# zik-pcb-gpu-f405.net
KiCad netlist of a schematic drawn in EAGLE
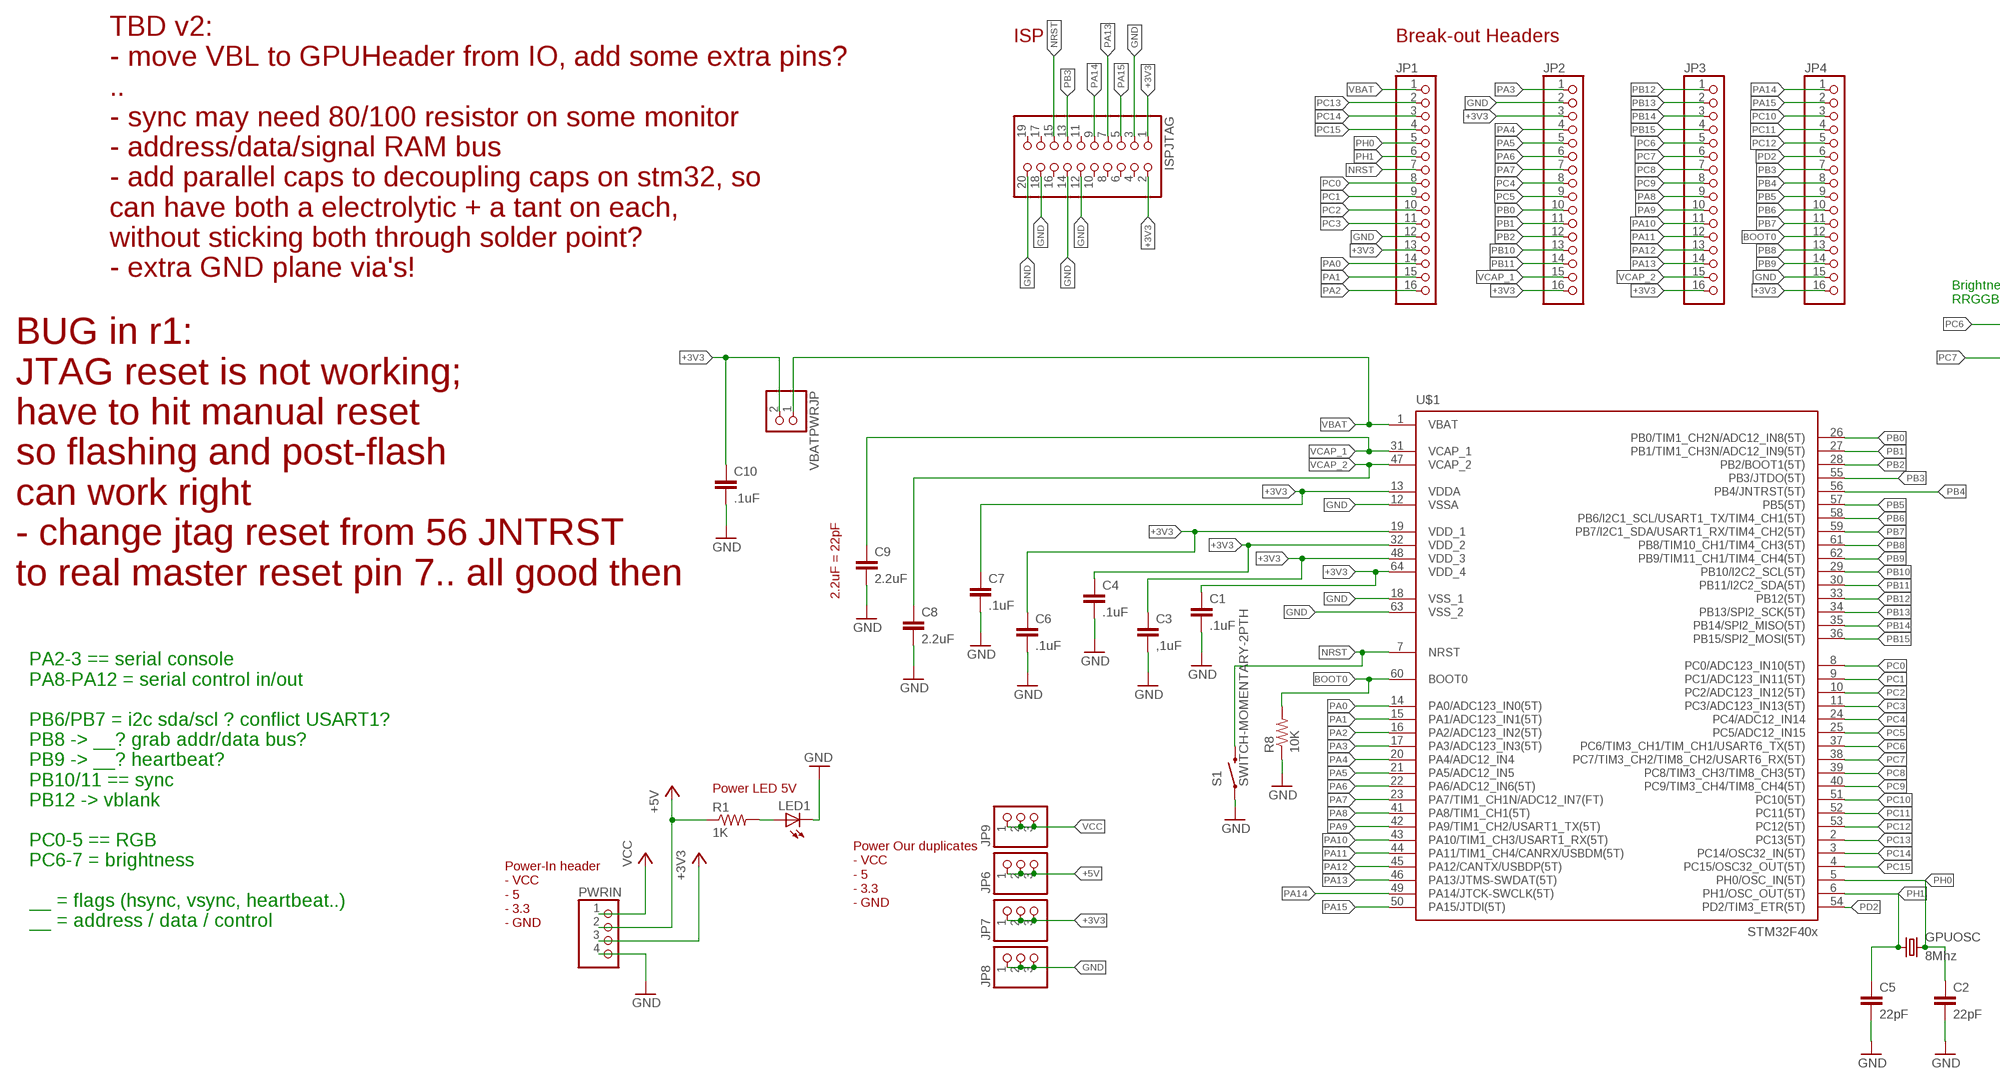
[diagram p0: schematic, sheet 1, part 1 of 2]
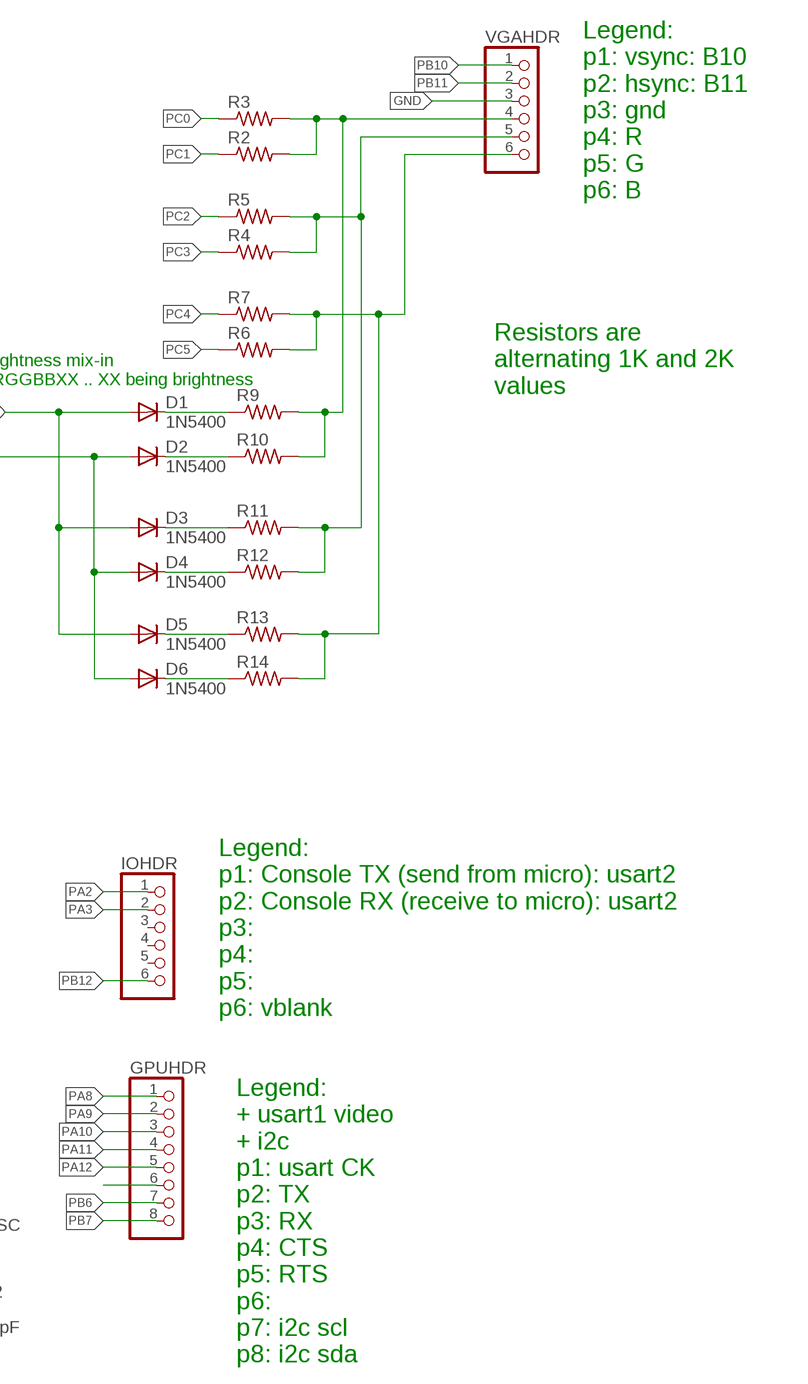
[diagram p1: schematic, sheet 1, part 2 of 2]

(export (version "E")
  (design (tool "Eeschema 10.0.6"))
  (components
    (comp (ref "C1")
      (value ".1uF")
      (footprint "eagle-import:C025-025X050")
      (libsource (lib "eagle-import") (part "C-EU025-025X050"))
    )
    (comp (ref "C2")
      (value "22pF")
      (footprint "eagle-import:C025-025X050")
      (libsource (lib "eagle-import") (part "C-EU025-025X050"))
    )
    (comp (ref "C3")
      (value ",1uF")
      (footprint "eagle-import:C025-025X050")
      (libsource (lib "eagle-import") (part "C-EU025-025X050"))
    )
    (comp (ref "C4")
      (value ".1uF")
      (footprint "eagle-import:C025-025X050")
      (libsource (lib "eagle-import") (part "C-EU025-025X050"))
    )
    (comp (ref "C5")
      (value "22pF")
      (footprint "eagle-import:C025-025X050")
      (libsource (lib "eagle-import") (part "C-EU025-025X050"))
    )
    (comp (ref "C6")
      (value ".1uF")
      (footprint "eagle-import:C025-025X050")
      (libsource (lib "eagle-import") (part "C-EU025-025X050"))
    )
    (comp (ref "C7")
      (value ".1uF")
      (footprint "eagle-import:C025-025X050")
      (libsource (lib "eagle-import") (part "C-EU025-025X050"))
    )
    (comp (ref "C8")
      (value "2.2uF")
      (footprint "eagle-import:C025-025X050")
      (libsource (lib "eagle-import") (part "C-EU025-025X050"))
    )
    (comp (ref "C9")
      (value "2.2uF")
      (footprint "eagle-import:C025-025X050")
      (libsource (lib "eagle-import") (part "C-EU025-025X050"))
    )
    (comp (ref "C10")
      (value ".1uF")
      (footprint "eagle-import:C025-025X050")
      (libsource (lib "eagle-import") (part "C-EU025-025X050"))
    )
    (comp (ref "D1")
      (value "1N5400")
      (footprint "eagle-import:DO201-15")
      (libsource (lib "eagle-import") (part "1N5400"))
    )
    (comp (ref "D2")
      (value "1N5400")
      (footprint "eagle-import:DO201-15")
      (libsource (lib "eagle-import") (part "1N5400"))
    )
    (comp (ref "D3")
      (value "1N5400")
      (footprint "eagle-import:DO201-15")
      (libsource (lib "eagle-import") (part "1N5400"))
    )
    (comp (ref "D4")
      (value "1N5400")
      (footprint "eagle-import:DO201-15")
      (libsource (lib "eagle-import") (part "1N5400"))
    )
    (comp (ref "D5")
      (value "1N5400")
      (footprint "eagle-import:DO201-15")
      (libsource (lib "eagle-import") (part "1N5400"))
    )
    (comp (ref "D6")
      (value "1N5400")
      (footprint "eagle-import:DO201-15")
      (libsource (lib "eagle-import") (part "1N5400"))
    )
    (comp (ref "GPUHDR")
      (value "PINHD-1X8")
      (footprint "eagle-import:1X08")
      (libsource (lib "eagle-import") (part "PINHD-1X8"))
    )
    (comp (ref "GPUOSC")
      (value "8Mhz")
      (footprint "eagle-import:HC49US")
      (libsource (lib "eagle-import") (part "CRYSTALHC49US"))
    )
    (comp (ref "IOHDR")
      (value "PINHD-1X6")
      (footprint "eagle-import:1X06")
      (libsource (lib "eagle-import") (part "PINHD-1X6"))
    )
    (comp (ref "ISPJTAG")
      (value "PINHD-2X10")
      (footprint "eagle-import:2X10")
      (libsource (lib "eagle-import") (part "PINHD-2X10"))
    )
    (comp (ref "JP1")
      (value "PINHD-1X16")
      (footprint "eagle-import:1X16")
      (libsource (lib "eagle-import") (part "PINHD-1X16"))
    )
    (comp (ref "JP2")
      (value "PINHD-1X16")
      (footprint "eagle-import:1X16")
      (libsource (lib "eagle-import") (part "PINHD-1X16"))
    )
    (comp (ref "JP3")
      (value "PINHD-1X16")
      (footprint "eagle-import:1X16")
      (libsource (lib "eagle-import") (part "PINHD-1X16"))
    )
    (comp (ref "JP4")
      (value "PINHD-1X16")
      (footprint "eagle-import:1X16")
      (libsource (lib "eagle-import") (part "PINHD-1X16"))
    )
    (comp (ref "JP6")
      (value "PINHD-1X3")
      (footprint "eagle-import:1X03")
      (libsource (lib "eagle-import") (part "PINHD-1X3"))
    )
    (comp (ref "JP7")
      (value "PINHD-1X3")
      (footprint "eagle-import:1X03")
      (libsource (lib "eagle-import") (part "PINHD-1X3"))
    )
    (comp (ref "JP8")
      (value "PINHD-1X3")
      (footprint "eagle-import:1X03")
      (libsource (lib "eagle-import") (part "PINHD-1X3"))
    )
    (comp (ref "JP9")
      (value "PINHD-1X3")
      (footprint "eagle-import:1X03")
      (libsource (lib "eagle-import") (part "PINHD-1X3"))
    )
    (comp (ref "LED1")
      (value "LED5MM")
      (footprint "eagle-import:LED5MM")
      (libsource (lib "eagle-import") (part "LED5MM"))
    )
    (comp (ref "PWRIN")
      (value "PINHD-1X4")
      (footprint "eagle-import:1X04")
      (libsource (lib "eagle-import") (part "PINHD-1X4"))
    )
    (comp (ref "R1")
      (value "1K")
      (footprint "eagle-import:0207_10")
      (libsource (lib "eagle-import") (part "R-US_0207/10"))
    )
    (comp (ref "R2")
      (value "R-US_0207/10")
      (footprint "eagle-import:0207_10")
      (libsource (lib "eagle-import") (part "R-US_0207/10"))
    )
    (comp (ref "R3")
      (value "R-US_0207/10")
      (footprint "eagle-import:0207_10")
      (libsource (lib "eagle-import") (part "R-US_0207/10"))
    )
    (comp (ref "R4")
      (value "R-US_0207/10")
      (footprint "eagle-import:0207_10")
      (libsource (lib "eagle-import") (part "R-US_0207/10"))
    )
    (comp (ref "R5")
      (value "R-US_0207/10")
      (footprint "eagle-import:0207_10")
      (libsource (lib "eagle-import") (part "R-US_0207/10"))
    )
    (comp (ref "R6")
      (value "R-US_0207/10")
      (footprint "eagle-import:0207_10")
      (libsource (lib "eagle-import") (part "R-US_0207/10"))
    )
    (comp (ref "R7")
      (value "R-US_0207/10")
      (footprint "eagle-import:0207_10")
      (libsource (lib "eagle-import") (part "R-US_0207/10"))
    )
    (comp (ref "R8")
      (value "10K")
      (footprint "eagle-import:0207_10")
      (libsource (lib "eagle-import") (part "R-US_0207/10"))
    )
    (comp (ref "R9")
      (value "R-US_0207/10")
      (footprint "eagle-import:0207_10")
      (libsource (lib "eagle-import") (part "R-US_0207/10"))
    )
    (comp (ref "R10")
      (value "R-US_0207/10")
      (footprint "eagle-import:0207_10")
      (libsource (lib "eagle-import") (part "R-US_0207/10"))
    )
    (comp (ref "R11")
      (value "R-US_0207/10")
      (footprint "eagle-import:0207_10")
      (libsource (lib "eagle-import") (part "R-US_0207/10"))
    )
    (comp (ref "R12")
      (value "R-US_0207/10")
      (footprint "eagle-import:0207_10")
      (libsource (lib "eagle-import") (part "R-US_0207/10"))
    )
    (comp (ref "R13")
      (value "R-US_0207/10")
      (footprint "eagle-import:0207_10")
      (libsource (lib "eagle-import") (part "R-US_0207/10"))
    )
    (comp (ref "R14")
      (value "R-US_0207/10")
      (footprint "eagle-import:0207_10")
      (libsource (lib "eagle-import") (part "R-US_0207/10"))
    )
    (comp (ref "S1")
      (value "SWITCH-MOMENTARY-2PTH")
      (footprint "eagle-import:TACTILE-PTH")
      (libsource (lib "eagle-import") (part "SWITCH-MOMENTARY-2PTH"))
    )
    (comp (ref "U$1")
      (value "STM32F405R")
      (footprint "eagle-import:TQFP64")
      (libsource (lib "eagle-import") (part "STM32F405R"))
    )
    (comp (ref "VBATPWRJP")
      (value "PINHD-1X2")
      (footprint "eagle-import:1X02")
      (libsource (lib "eagle-import") (part "PINHD-1X2"))
    )
    (comp (ref "VGAHDR")
      (value "PINHD-1X6")
      (footprint "eagle-import:1X06")
      (libsource (lib "eagle-import") (part "PINHD-1X6"))
    )
  )
  (nets
    (net (code "1") (name "+3V3") (class "Default")
      (node (ref "C1") (pin "1") (pinfunction "1_1") (pintype "passive"))
      (node (ref "C10") (pin "1") (pinfunction "1_1") (pintype "passive"))
      (node (ref "C3") (pin "1") (pinfunction "1_1") (pintype "passive"))
      (node (ref "C4") (pin "1") (pinfunction "1_1") (pintype "passive"))
      (node (ref "C6") (pin "1") (pinfunction "1_1") (pintype "passive"))
      (node (ref "C7") (pin "1") (pinfunction "1_1") (pintype "passive"))
      (node (ref "ISPJTAG") (pin "1") (pinfunction "1_1") (pintype "passive"))
      (node (ref "ISPJTAG") (pin "2") (pinfunction "2_2") (pintype "passive"))
      (node (ref "JP1") (pin "13") (pinfunction "13_13") (pintype "passive"))
      (node (ref "JP2") (pin "16") (pinfunction "16_16") (pintype "passive"))
      (node (ref "JP2") (pin "3") (pinfunction "3_3") (pintype "passive"))
      (node (ref "JP3") (pin "16") (pinfunction "16_16") (pintype "passive"))
      (node (ref "JP4") (pin "16") (pinfunction "16_16") (pintype "passive"))
      (node (ref "JP7") (pin "1") (pinfunction "1_1") (pintype "passive"))
      (node (ref "JP7") (pin "2") (pinfunction "2_2") (pintype "passive"))
      (node (ref "JP7") (pin "3") (pinfunction "3_3") (pintype "passive"))
      (node (ref "PWRIN") (pin "3") (pinfunction "3_3") (pintype "passive"))
      (node (ref "U$1") (pin "13") (pinfunction "VDDA_13") (pintype "bidirectional"))
      (node (ref "U$1") (pin "19") (pinfunction "VDD_1_19") (pintype "bidirectional"))
      (node (ref "U$1") (pin "32") (pinfunction "VDD_2_32") (pintype "bidirectional"))
      (node (ref "U$1") (pin "48") (pinfunction "VDD_3_48") (pintype "bidirectional"))
      (node (ref "U$1") (pin "64") (pinfunction "VDD_4_64") (pintype "bidirectional"))
      (node (ref "VBATPWRJP") (pin "2") (pinfunction "2_2") (pintype "passive"))
    )
    (net (code "2") (name "+5V") (class "Default")
      (node (ref "JP6") (pin "1") (pinfunction "1_1") (pintype "passive"))
      (node (ref "JP6") (pin "2") (pinfunction "2_2") (pintype "passive"))
      (node (ref "JP6") (pin "3") (pinfunction "3_3") (pintype "passive"))
      (node (ref "PWRIN") (pin "2") (pinfunction "2_2") (pintype "passive"))
      (node (ref "R1") (pin "1") (pinfunction "1_1") (pintype "passive"))
    )
    (net (code "3") (name "BOOT0") (class "Default")
      (node (ref "JP4") (pin "12") (pinfunction "12_12") (pintype "passive"))
      (node (ref "R8") (pin "2") (pinfunction "2_2") (pintype "passive"))
      (node (ref "U$1") (pin "60") (pinfunction "BOOT0_60") (pintype "bidirectional"))
    )
    (net (code "4") (name "GND") (class "Default")
      (node (ref "C1") (pin "2") (pinfunction "2_2") (pintype "passive"))
      (node (ref "C10") (pin "2") (pinfunction "2_2") (pintype "passive"))
      (node (ref "C2") (pin "2") (pinfunction "2_2") (pintype "passive"))
      (node (ref "C3") (pin "2") (pinfunction "2_2") (pintype "passive"))
      (node (ref "C4") (pin "2") (pinfunction "2_2") (pintype "passive"))
      (node (ref "C5") (pin "2") (pinfunction "2_2") (pintype "passive"))
      (node (ref "C6") (pin "2") (pinfunction "2_2") (pintype "passive"))
      (node (ref "C7") (pin "2") (pinfunction "2_2") (pintype "passive"))
      (node (ref "C8") (pin "2") (pinfunction "2_2") (pintype "passive"))
      (node (ref "C9") (pin "2") (pinfunction "2_2") (pintype "passive"))
      (node (ref "ISPJTAG") (pin "12") (pinfunction "12_12") (pintype "passive"))
      (node (ref "ISPJTAG") (pin "14") (pinfunction "14_14") (pintype "passive"))
      (node (ref "ISPJTAG") (pin "18") (pinfunction "18_18") (pintype "passive"))
      (node (ref "ISPJTAG") (pin "20") (pinfunction "20_20") (pintype "passive"))
      (node (ref "ISPJTAG") (pin "3") (pinfunction "3_3") (pintype "passive"))
      (node (ref "JP1") (pin "12") (pinfunction "12_12") (pintype "passive"))
      (node (ref "JP2") (pin "2") (pinfunction "2_2") (pintype "passive"))
      (node (ref "JP4") (pin "15") (pinfunction "15_15") (pintype "passive"))
      (node (ref "JP8") (pin "1") (pinfunction "1_1") (pintype "passive"))
      (node (ref "JP8") (pin "2") (pinfunction "2_2") (pintype "passive"))
      (node (ref "JP8") (pin "3") (pinfunction "3_3") (pintype "passive"))
      (node (ref "LED1") (pin "K") (pinfunction "C_K") (pintype "passive"))
      (node (ref "PWRIN") (pin "4") (pinfunction "4_4") (pintype "passive"))
      (node (ref "R8") (pin "1") (pinfunction "1_1") (pintype "passive"))
      (node (ref "S1") (pin "1") (pinfunction "1_1") (pintype "passive"))
      (node (ref "U$1") (pin "12") (pinfunction "VSSA_12") (pintype "bidirectional"))
      (node (ref "U$1") (pin "18") (pinfunction "VSS_1_18") (pintype "bidirectional"))
      (node (ref "U$1") (pin "63") (pinfunction "VSS_2_63") (pintype "bidirectional"))
      (node (ref "VGAHDR") (pin "3") (pinfunction "3_3") (pintype "passive"))
    )
    (net (code "5") (name "NRST") (class "Default")
      (node (ref "ISPJTAG") (pin "15") (pinfunction "15_15") (pintype "passive"))
      (node (ref "JP1") (pin "7") (pinfunction "7_7") (pintype "passive"))
      (node (ref "S1") (pin "3") (pinfunction "2_3") (pintype "passive"))
      (node (ref "U$1") (pin "7") (pinfunction "NRST_7") (pintype "bidirectional"))
    )
    (net (code "6") (name "Net-(D1-PadC)") (class "Default")
      (node (ref "D1") (pin "C") (pinfunction "C_C") (pintype "passive"))
      (node (ref "R9") (pin "1") (pinfunction "1_1") (pintype "passive"))
    )
    (net (code "7") (name "Net-(D2-PadC)") (class "Default")
      (node (ref "D2") (pin "C") (pinfunction "C_C") (pintype "passive"))
      (node (ref "R10") (pin "1") (pinfunction "1_1") (pintype "passive"))
    )
    (net (code "8") (name "Net-(D3-PadC)") (class "Default")
      (node (ref "D3") (pin "C") (pinfunction "C_C") (pintype "passive"))
      (node (ref "R11") (pin "1") (pinfunction "1_1") (pintype "passive"))
    )
    (net (code "9") (name "Net-(D4-PadC)") (class "Default")
      (node (ref "D4") (pin "C") (pinfunction "C_C") (pintype "passive"))
      (node (ref "R12") (pin "1") (pinfunction "1_1") (pintype "passive"))
    )
    (net (code "10") (name "Net-(D5-PadC)") (class "Default")
      (node (ref "D5") (pin "C") (pinfunction "C_C") (pintype "passive"))
      (node (ref "R13") (pin "1") (pinfunction "1_1") (pintype "passive"))
    )
    (net (code "11") (name "Net-(D6-PadC)") (class "Default")
      (node (ref "D6") (pin "C") (pinfunction "C_C") (pintype "passive"))
      (node (ref "R14") (pin "1") (pinfunction "1_1") (pintype "passive"))
    )
    (net (code "12") (name "Net-(LED1-PadA)") (class "Default")
      (node (ref "LED1") (pin "A") (pinfunction "A_A") (pintype "passive"))
      (node (ref "R1") (pin "2") (pinfunction "2_2") (pintype "passive"))
    )
    (net (code "13") (name "Net-(R10-Pad2)") (class "Default")
      (node (ref "R10") (pin "2") (pinfunction "2_2") (pintype "passive"))
      (node (ref "R2") (pin "2") (pinfunction "2_2") (pintype "passive"))
      (node (ref "R3") (pin "2") (pinfunction "2_2") (pintype "passive"))
      (node (ref "R9") (pin "2") (pinfunction "2_2") (pintype "passive"))
      (node (ref "VGAHDR") (pin "4") (pinfunction "4_4") (pintype "passive"))
    )
    (net (code "14") (name "Net-(R11-Pad2)") (class "Default")
      (node (ref "R11") (pin "2") (pinfunction "2_2") (pintype "passive"))
      (node (ref "R12") (pin "2") (pinfunction "2_2") (pintype "passive"))
      (node (ref "R4") (pin "2") (pinfunction "2_2") (pintype "passive"))
      (node (ref "R5") (pin "2") (pinfunction "2_2") (pintype "passive"))
      (node (ref "VGAHDR") (pin "5") (pinfunction "5_5") (pintype "passive"))
    )
    (net (code "15") (name "Net-(R13-Pad2)") (class "Default")
      (node (ref "R13") (pin "2") (pinfunction "2_2") (pintype "passive"))
      (node (ref "R14") (pin "2") (pinfunction "2_2") (pintype "passive"))
      (node (ref "R6") (pin "2") (pinfunction "2_2") (pintype "passive"))
      (node (ref "R7") (pin "2") (pinfunction "2_2") (pintype "passive"))
      (node (ref "VGAHDR") (pin "6") (pinfunction "6_6") (pintype "passive"))
    )
    (net (code "16") (name "PA0") (class "Default")
      (node (ref "JP1") (pin "14") (pinfunction "14_14") (pintype "passive"))
      (node (ref "U$1") (pin "14") (pinfunction "PA0/ADC123_IN0(5T)_14") (pintype "bidirectional"))
    )
    (net (code "17") (name "PA1") (class "Default")
      (node (ref "JP1") (pin "15") (pinfunction "15_15") (pintype "passive"))
      (node (ref "U$1") (pin "15") (pinfunction "PA1/ADC123_IN1(5T)_15") (pintype "bidirectional"))
    )
    (net (code "18") (name "PA2") (class "Default")
      (node (ref "IOHDR") (pin "1") (pinfunction "1_1") (pintype "passive"))
      (node (ref "JP1") (pin "16") (pinfunction "16_16") (pintype "passive"))
      (node (ref "U$1") (pin "16") (pinfunction "PA2/ADC123_IN2(5T)_16") (pintype "bidirectional"))
    )
    (net (code "19") (name "PA3") (class "Default")
      (node (ref "IOHDR") (pin "2") (pinfunction "2_2") (pintype "passive"))
      (node (ref "JP2") (pin "1") (pinfunction "1_1") (pintype "passive"))
      (node (ref "U$1") (pin "17") (pinfunction "PA3/ADC123_IN3(5T)_17") (pintype "bidirectional"))
    )
    (net (code "20") (name "PA4") (class "Default")
      (node (ref "JP2") (pin "4") (pinfunction "4_4") (pintype "passive"))
      (node (ref "U$1") (pin "20") (pinfunction "PA4/ADC12_IN4_20") (pintype "bidirectional"))
    )
    (net (code "21") (name "PA5") (class "Default")
      (node (ref "JP2") (pin "5") (pinfunction "5_5") (pintype "passive"))
      (node (ref "U$1") (pin "21") (pinfunction "PA5/ADC12_IN5_21") (pintype "bidirectional"))
    )
    (net (code "22") (name "PA6") (class "Default")
      (node (ref "JP2") (pin "6") (pinfunction "6_6") (pintype "passive"))
      (node (ref "U$1") (pin "22") (pinfunction "PA6/ADC12_IN6(5T)_22") (pintype "bidirectional"))
    )
    (net (code "23") (name "PA7") (class "Default")
      (node (ref "JP2") (pin "7") (pinfunction "7_7") (pintype "passive"))
      (node (ref "U$1") (pin "23") (pinfunction "PA7/TIM1_CH1N/ADC12_IN7(FT)_23") (pintype "bidirectional"))
    )
    (net (code "24") (name "PA8") (class "Default")
      (node (ref "GPUHDR") (pin "1") (pinfunction "1_1") (pintype "passive"))
      (node (ref "JP3") (pin "9") (pinfunction "9_9") (pintype "passive"))
      (node (ref "U$1") (pin "41") (pinfunction "PA8/TIM1_CH1(5T)_41") (pintype "bidirectional"))
    )
    (net (code "25") (name "PA9") (class "Default")
      (node (ref "GPUHDR") (pin "2") (pinfunction "2_2") (pintype "passive"))
      (node (ref "JP3") (pin "10") (pinfunction "10_10") (pintype "passive"))
      (node (ref "U$1") (pin "42") (pinfunction "PA9/TIM1_CH2/USART1_TX(5T)_42") (pintype "bidirectional"))
    )
    (net (code "26") (name "PA10") (class "Default")
      (node (ref "GPUHDR") (pin "3") (pinfunction "3_3") (pintype "passive"))
      (node (ref "JP3") (pin "11") (pinfunction "11_11") (pintype "passive"))
      (node (ref "U$1") (pin "43") (pinfunction "PA10/TIM1_CH3/USART1_RX(5T)_43") (pintype "bidirectional"))
    )
    (net (code "27") (name "PA11") (class "Default")
      (node (ref "GPUHDR") (pin "4") (pinfunction "4_4") (pintype "passive"))
      (node (ref "JP3") (pin "12") (pinfunction "12_12") (pintype "passive"))
      (node (ref "U$1") (pin "44") (pinfunction "PA11/TIM1_CH4/CANRX/USBDM(5T)_44") (pintype "bidirectional"))
    )
    (net (code "28") (name "PA12") (class "Default")
      (node (ref "GPUHDR") (pin "5") (pinfunction "5_5") (pintype "passive"))
      (node (ref "JP3") (pin "13") (pinfunction "13_13") (pintype "passive"))
      (node (ref "U$1") (pin "45") (pinfunction "PA12/CANTX/USBDP(5T)_45") (pintype "bidirectional"))
    )
    (net (code "29") (name "PA13") (class "Default")
      (node (ref "ISPJTAG") (pin "7") (pinfunction "7_7") (pintype "passive"))
      (node (ref "JP3") (pin "14") (pinfunction "14_14") (pintype "passive"))
      (node (ref "U$1") (pin "46") (pinfunction "PA13/JTMS-SWDAT(5T)_46") (pintype "bidirectional"))
    )
    (net (code "30") (name "PA14") (class "Default")
      (node (ref "ISPJTAG") (pin "9") (pinfunction "9_9") (pintype "passive"))
      (node (ref "JP4") (pin "1") (pinfunction "1_1") (pintype "passive"))
      (node (ref "U$1") (pin "49") (pinfunction "PA14/JTCK-SWCLK(5T)_49") (pintype "bidirectional"))
    )
    (net (code "31") (name "PA15") (class "Default")
      (node (ref "ISPJTAG") (pin "5") (pinfunction "5_5") (pintype "passive"))
      (node (ref "JP4") (pin "2") (pinfunction "2_2") (pintype "passive"))
      (node (ref "U$1") (pin "50") (pinfunction "PA15/JTDI(5T)_50") (pintype "bidirectional"))
    )
    (net (code "32") (name "PB0") (class "Default")
      (node (ref "JP2") (pin "10") (pinfunction "10_10") (pintype "passive"))
      (node (ref "U$1") (pin "26") (pinfunction "PB0/TIM1_CH2N/ADC12_IN8(5T)_26") (pintype "bidirectional"))
    )
    (net (code "33") (name "PB1") (class "Default")
      (node (ref "JP2") (pin "11") (pinfunction "11_11") (pintype "passive"))
      (node (ref "U$1") (pin "27") (pinfunction "PB1/TIM1_CH3N/ADC12_IN9(5T)_27") (pintype "bidirectional"))
    )
    (net (code "34") (name "PB2") (class "Default")
      (node (ref "JP2") (pin "12") (pinfunction "12_12") (pintype "passive"))
      (node (ref "U$1") (pin "28") (pinfunction "PB2/BOOT1(5T)_28") (pintype "bidirectional"))
    )
    (net (code "35") (name "PB3") (class "Default")
      (node (ref "ISPJTAG") (pin "13") (pinfunction "13_13") (pintype "passive"))
      (node (ref "JP4") (pin "7") (pinfunction "7_7") (pintype "passive"))
      (node (ref "U$1") (pin "55") (pinfunction "PB3/JTDO(5T)_55") (pintype "bidirectional"))
    )
    (net (code "36") (name "PB4") (class "Default")
      (node (ref "JP4") (pin "8") (pinfunction "8_8") (pintype "passive"))
      (node (ref "U$1") (pin "56") (pinfunction "PB4/JNTRST(5T)_56") (pintype "bidirectional"))
    )
    (net (code "37") (name "PB5") (class "Default")
      (node (ref "JP4") (pin "9") (pinfunction "9_9") (pintype "passive"))
      (node (ref "U$1") (pin "57") (pinfunction "PB5(5T)_57") (pintype "bidirectional"))
    )
    (net (code "38") (name "PB6") (class "Default")
      (node (ref "GPUHDR") (pin "7") (pinfunction "7_7") (pintype "passive"))
      (node (ref "JP4") (pin "10") (pinfunction "10_10") (pintype "passive"))
      (node (ref "U$1") (pin "58") (pinfunction "PB6/I2C1_SCL/USART1_TX/TIM4_CH1(5T)_58") (pintype "bidirectional"))
    )
    (net (code "39") (name "PB7") (class "Default")
      (node (ref "GPUHDR") (pin "8") (pinfunction "8_8") (pintype "passive"))
      (node (ref "JP4") (pin "11") (pinfunction "11_11") (pintype "passive"))
      (node (ref "U$1") (pin "59") (pinfunction "PB7/I2C1_SDA/USART1_RX/TIM4_CH2(5T)_59") (pintype "bidirectional"))
    )
    (net (code "40") (name "PB8") (class "Default")
      (node (ref "JP4") (pin "13") (pinfunction "13_13") (pintype "passive"))
      (node (ref "U$1") (pin "61") (pinfunction "PB8/TIM10_CH1/TIM4_CH3(5T)_61") (pintype "bidirectional"))
    )
    (net (code "41") (name "PB9") (class "Default")
      (node (ref "JP4") (pin "14") (pinfunction "14_14") (pintype "passive"))
      (node (ref "U$1") (pin "62") (pinfunction "PB9/TIM11_CH1/TIM4_CH4(5T)_62") (pintype "bidirectional"))
    )
    (net (code "42") (name "PB10") (class "Default")
      (node (ref "JP2") (pin "13") (pinfunction "13_13") (pintype "passive"))
      (node (ref "U$1") (pin "29") (pinfunction "PB10/I2C2_SCL(5T)_29") (pintype "bidirectional"))
      (node (ref "VGAHDR") (pin "1") (pinfunction "1_1") (pintype "passive"))
    )
    (net (code "43") (name "PB11") (class "Default")
      (node (ref "JP2") (pin "14") (pinfunction "14_14") (pintype "passive"))
      (node (ref "U$1") (pin "30") (pinfunction "PB11/I2C2_SDA(5T)_30") (pintype "bidirectional"))
      (node (ref "VGAHDR") (pin "2") (pinfunction "2_2") (pintype "passive"))
    )
    (net (code "44") (name "PB12") (class "Default")
      (node (ref "IOHDR") (pin "6") (pinfunction "6_6") (pintype "passive"))
      (node (ref "JP3") (pin "1") (pinfunction "1_1") (pintype "passive"))
      (node (ref "U$1") (pin "33") (pinfunction "PB12(5T)_33") (pintype "bidirectional"))
    )
    (net (code "45") (name "PB13") (class "Default")
      (node (ref "JP3") (pin "2") (pinfunction "2_2") (pintype "passive"))
      (node (ref "U$1") (pin "34") (pinfunction "PB13/SPI2_SCK(5T)_34") (pintype "bidirectional"))
    )
    (net (code "46") (name "PB14") (class "Default")
      (node (ref "JP3") (pin "3") (pinfunction "3_3") (pintype "passive"))
      (node (ref "U$1") (pin "35") (pinfunction "PB14/SPI2_MISO(5T)_35") (pintype "bidirectional"))
    )
    (net (code "47") (name "PB15") (class "Default")
      (node (ref "JP3") (pin "4") (pinfunction "4_4") (pintype "passive"))
      (node (ref "U$1") (pin "36") (pinfunction "PB15/SPI2_MOSI(5T)_36") (pintype "bidirectional"))
    )
    (net (code "48") (name "PC0") (class "Default")
      (node (ref "JP1") (pin "8") (pinfunction "8_8") (pintype "passive"))
      (node (ref "R3") (pin "1") (pinfunction "1_1") (pintype "passive"))
      (node (ref "U$1") (pin "8") (pinfunction "PC0/ADC123_IN10(5T)_8") (pintype "bidirectional"))
    )
    (net (code "49") (name "PC1") (class "Default")
      (node (ref "JP1") (pin "9") (pinfunction "9_9") (pintype "passive"))
      (node (ref "R2") (pin "1") (pinfunction "1_1") (pintype "passive"))
      (node (ref "U$1") (pin "9") (pinfunction "PC1/ADC123_IN11(5T)_9") (pintype "bidirectional"))
    )
    (net (code "50") (name "PC2") (class "Default")
      (node (ref "JP1") (pin "10") (pinfunction "10_10") (pintype "passive"))
      (node (ref "R5") (pin "1") (pinfunction "1_1") (pintype "passive"))
      (node (ref "U$1") (pin "10") (pinfunction "PC2/ADC123_IN12(5T)_10") (pintype "bidirectional"))
    )
    (net (code "51") (name "PC3") (class "Default")
      (node (ref "JP1") (pin "11") (pinfunction "11_11") (pintype "passive"))
      (node (ref "R4") (pin "1") (pinfunction "1_1") (pintype "passive"))
      (node (ref "U$1") (pin "11") (pinfunction "PC3/ADC123_IN13(5T)_11") (pintype "bidirectional"))
    )
    (net (code "52") (name "PC4") (class "Default")
      (node (ref "JP2") (pin "8") (pinfunction "8_8") (pintype "passive"))
      (node (ref "R7") (pin "1") (pinfunction "1_1") (pintype "passive"))
      (node (ref "U$1") (pin "24") (pinfunction "PC4/ADC12_IN14_24") (pintype "bidirectional"))
    )
    (net (code "53") (name "PC5") (class "Default")
      (node (ref "JP2") (pin "9") (pinfunction "9_9") (pintype "passive"))
      (node (ref "R6") (pin "1") (pinfunction "1_1") (pintype "passive"))
      (node (ref "U$1") (pin "25") (pinfunction "PC5/ADC12_IN15_25") (pintype "bidirectional"))
    )
    (net (code "54") (name "PC6") (class "Default")
      (node (ref "D1") (pin "A") (pinfunction "A_A") (pintype "passive"))
      (node (ref "D3") (pin "A") (pinfunction "A_A") (pintype "passive"))
      (node (ref "D5") (pin "A") (pinfunction "A_A") (pintype "passive"))
      (node (ref "JP3") (pin "5") (pinfunction "5_5") (pintype "passive"))
      (node (ref "U$1") (pin "37") (pinfunction "PC6/TIM3_CH1/TIM_CH1/USART6_TX(5T)_37") (pintype "bidirectional"))
    )
    (net (code "55") (name "PC7") (class "Default")
      (node (ref "D2") (pin "A") (pinfunction "A_A") (pintype "passive"))
      (node (ref "D4") (pin "A") (pinfunction "A_A") (pintype "passive"))
      (node (ref "D6") (pin "A") (pinfunction "A_A") (pintype "passive"))
      (node (ref "JP3") (pin "6") (pinfunction "6_6") (pintype "passive"))
      (node (ref "U$1") (pin "38") (pinfunction "PC7/TIM3_CH2/TIM8_CH2/USART6_RX(5T)_38") (pintype "bidirectional"))
    )
    (net (code "56") (name "PC8") (class "Default")
      (node (ref "JP3") (pin "7") (pinfunction "7_7") (pintype "passive"))
      (node (ref "U$1") (pin "39") (pinfunction "PC8/TIM3_CH3/TIM8_CH3(5T)_39") (pintype "bidirectional"))
    )
    (net (code "57") (name "PC9") (class "Default")
      (node (ref "JP3") (pin "8") (pinfunction "8_8") (pintype "passive"))
      (node (ref "U$1") (pin "40") (pinfunction "PC9/TIM3_CH4/TIM8_CH4(5T)_40") (pintype "bidirectional"))
    )
    (net (code "58") (name "PC10") (class "Default")
      (node (ref "JP4") (pin "3") (pinfunction "3_3") (pintype "passive"))
      (node (ref "U$1") (pin "51") (pinfunction "PC10(5T)_51") (pintype "bidirectional"))
    )
    (net (code "59") (name "PC11") (class "Default")
      (node (ref "JP4") (pin "4") (pinfunction "4_4") (pintype "passive"))
      (node (ref "U$1") (pin "52") (pinfunction "PC11(5T)_52") (pintype "bidirectional"))
    )
    (net (code "60") (name "PC12") (class "Default")
      (node (ref "JP4") (pin "5") (pinfunction "5_5") (pintype "passive"))
      (node (ref "U$1") (pin "53") (pinfunction "PC12(5T)_53") (pintype "bidirectional"))
    )
    (net (code "61") (name "PC13") (class "Default")
      (node (ref "JP1") (pin "2") (pinfunction "2_2") (pintype "passive"))
      (node (ref "U$1") (pin "2") (pinfunction "PC13(5T)_2") (pintype "bidirectional"))
    )
    (net (code "62") (name "PC14") (class "Default")
      (node (ref "JP1") (pin "3") (pinfunction "3_3") (pintype "passive"))
      (node (ref "U$1") (pin "3") (pinfunction "PC14/OSC32_IN(5T)_3") (pintype "bidirectional"))
    )
    (net (code "63") (name "PC15") (class "Default")
      (node (ref "JP1") (pin "4") (pinfunction "4_4") (pintype "passive"))
      (node (ref "U$1") (pin "4") (pinfunction "PC15/OSC32_OUT(5T)_4") (pintype "bidirectional"))
    )
    (net (code "64") (name "PD2") (class "Default")
      (node (ref "JP4") (pin "6") (pinfunction "6_6") (pintype "passive"))
      (node (ref "U$1") (pin "54") (pinfunction "PD2/TIM3_ETR(5T)_54") (pintype "bidirectional"))
    )
    (net (code "65") (name "PH0") (class "Default")
      (node (ref "C2") (pin "1") (pinfunction "1_1") (pintype "passive"))
      (node (ref "GPUOSC") (pin "2") (pinfunction "2_2") (pintype "passive"))
      (node (ref "JP1") (pin "5") (pinfunction "5_5") (pintype "passive"))
      (node (ref "U$1") (pin "5") (pinfunction "PH0/OSC_IN(5T)_5") (pintype "bidirectional"))
    )
    (net (code "66") (name "PH1") (class "Default")
      (node (ref "C5") (pin "1") (pinfunction "1_1") (pintype "passive"))
      (node (ref "GPUOSC") (pin "1") (pinfunction "1_1") (pintype "passive"))
      (node (ref "JP1") (pin "6") (pinfunction "6_6") (pintype "passive"))
      (node (ref "U$1") (pin "6") (pinfunction "PH1/OSC_OUT(5T)_6") (pintype "bidirectional"))
    )
    (net (code "67") (name "VBAT") (class "Default")
      (node (ref "JP1") (pin "1") (pinfunction "1_1") (pintype "passive"))
      (node (ref "U$1") (pin "1") (pinfunction "VBAT_1") (pintype "bidirectional"))
      (node (ref "VBATPWRJP") (pin "1") (pinfunction "1_1") (pintype "passive"))
    )
    (net (code "68") (name "VCAP_1") (class "Default")
      (node (ref "C9") (pin "1") (pinfunction "1_1") (pintype "passive"))
      (node (ref "JP2") (pin "15") (pinfunction "15_15") (pintype "passive"))
      (node (ref "U$1") (pin "31") (pinfunction "VCAP_1_31") (pintype "bidirectional"))
    )
    (net (code "69") (name "VCAP_2") (class "Default")
      (node (ref "C8") (pin "1") (pinfunction "1_1") (pintype "passive"))
      (node (ref "JP3") (pin "15") (pinfunction "15_15") (pintype "passive"))
      (node (ref "U$1") (pin "47") (pinfunction "VCAP_2_47") (pintype "bidirectional"))
    )
    (net (code "70") (name "VCC") (class "Default")
      (node (ref "JP9") (pin "1") (pinfunction "1_1") (pintype "passive"))
      (node (ref "JP9") (pin "2") (pinfunction "2_2") (pintype "passive"))
      (node (ref "JP9") (pin "3") (pinfunction "3_3") (pintype "passive"))
      (node (ref "PWRIN") (pin "1") (pinfunction "1_1") (pintype "passive"))
    )
    (net (code "71") (name "unconnected-(GPUHDR-Pad6)") (class "Default")
      (node (ref "GPUHDR") (pin "6") (pinfunction "6_6") (pintype "passive"))
    )
    (net (code "72") (name "unconnected-(IOHDR-Pad3)") (class "Default")
      (node (ref "IOHDR") (pin "3") (pinfunction "3_3") (pintype "passive"))
    )
    (net (code "73") (name "unconnected-(IOHDR-Pad4)") (class "Default")
      (node (ref "IOHDR") (pin "4") (pinfunction "4_4") (pintype "passive"))
    )
    (net (code "74") (name "unconnected-(IOHDR-Pad5)") (class "Default")
      (node (ref "IOHDR") (pin "5") (pinfunction "5_5") (pintype "passive"))
    )
    (net (code "75") (name "unconnected-(ISPJTAG-Pad4)") (class "Default")
      (node (ref "ISPJTAG") (pin "4") (pinfunction "4_4") (pintype "passive"))
    )
    (net (code "76") (name "unconnected-(ISPJTAG-Pad6)") (class "Default")
      (node (ref "ISPJTAG") (pin "6") (pinfunction "6_6") (pintype "passive"))
    )
    (net (code "77") (name "unconnected-(ISPJTAG-Pad8)") (class "Default")
      (node (ref "ISPJTAG") (pin "8") (pinfunction "8_8") (pintype "passive"))
    )
    (net (code "78") (name "unconnected-(ISPJTAG-Pad10)") (class "Default")
      (node (ref "ISPJTAG") (pin "10") (pinfunction "10_10") (pintype "passive"))
    )
    (net (code "79") (name "unconnected-(ISPJTAG-Pad11)") (class "Default")
      (node (ref "ISPJTAG") (pin "11") (pinfunction "11_11") (pintype "passive"))
    )
    (net (code "80") (name "unconnected-(ISPJTAG-Pad16)") (class "Default")
      (node (ref "ISPJTAG") (pin "16") (pinfunction "16_16") (pintype "passive"))
    )
    (net (code "81") (name "unconnected-(ISPJTAG-Pad17)") (class "Default")
      (node (ref "ISPJTAG") (pin "17") (pinfunction "17_17") (pintype "passive"))
    )
    (net (code "82") (name "unconnected-(ISPJTAG-Pad19)") (class "Default")
      (node (ref "ISPJTAG") (pin "19") (pinfunction "19_19") (pintype "passive"))
    )
  )
)
